# SO-16.net
KiCad netlist of a schematic drawn in EAGLE
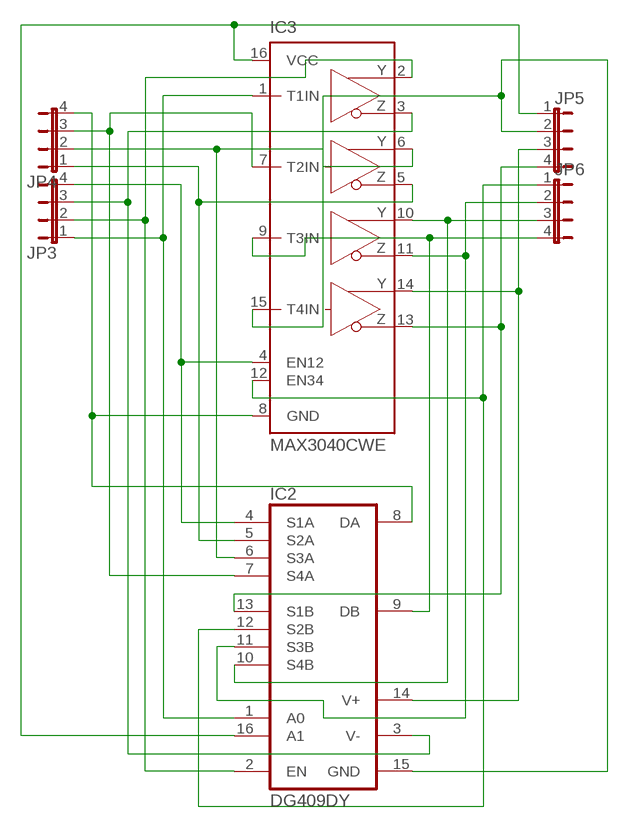
[diagram p0: schematic, sheet 1]

(export (version "E")
  (design (tool "Eeschema 10.0.6"))
  (components
    (comp (ref "IC2")
      (value "DG409DY")
      (footprint "eagle-import:SO16")
      (fields (field (name "MF") "MAXIM"))
      (libsource (lib "eagle-import") (part "DG409DY"))
    )
    (comp (ref "IC3")
      (value "MAX3040CWE")
      (footprint "eagle-import:SO16L")
      (fields (field (name "MPN") "MAX3040CWE+"))
      (libsource (lib "eagle-import") (part "MAX30WE40C"))
    )
    (comp (ref "JP3")
      (value "JP4E")
      (footprint "eagle-import:JP4")
      (libsource (lib "eagle-import") (part "JP4E"))
    )
    (comp (ref "JP4")
      (value "JP4E")
      (footprint "eagle-import:JP4")
      (libsource (lib "eagle-import") (part "JP4E"))
    )
    (comp (ref "JP5")
      (value "JP4E")
      (footprint "eagle-import:JP4")
      (libsource (lib "eagle-import") (part "JP4E"))
    )
    (comp (ref "JP6")
      (value "JP4E")
      (footprint "eagle-import:JP4")
      (libsource (lib "eagle-import") (part "JP4E"))
    )
  )
  (nets
    (net (code "1") (name "Net-(IC2-A0)") (class "Default")
      (node (ref "IC2") (pin "1") (pinfunction "A0_1") (pintype "input"))
      (node (ref "IC3") (pin "1") (pinfunction "T1IN_1") (pintype "input"))
      (node (ref "JP3") (pin "1") (pinfunction "1_1") (pintype "passive"))
    )
    (net (code "2") (name "Net-(IC2-A1)") (class "Default")
      (node (ref "IC2") (pin "16") (pinfunction "A1_16") (pintype "input"))
      (node (ref "IC3") (pin "16") (pinfunction "VCC_16") (pintype "power_in"))
      (node (ref "JP5") (pin "1") (pinfunction "1_1") (pintype "passive"))
    )
    (net (code "3") (name "Net-(IC2-DA)") (class "Default")
      (node (ref "IC2") (pin "8") (pinfunction "DA_8") (pintype "passive"))
      (node (ref "IC3") (pin "8") (pinfunction "GND_8") (pintype "power_in"))
      (node (ref "JP4") (pin "4") (pinfunction "4_4") (pintype "passive"))
    )
    (net (code "4") (name "Net-(IC2-DB)") (class "Default")
      (node (ref "IC2") (pin "9") (pinfunction "DB_9") (pintype "passive"))
      (node (ref "IC3") (pin "9") (pinfunction "T3IN_9") (pintype "input"))
      (node (ref "JP6") (pin "4") (pinfunction "4_4") (pintype "passive"))
    )
    (net (code "5") (name "Net-(IC2-EN)") (class "Default")
      (node (ref "IC2") (pin "2") (pinfunction "EN_2") (pintype "input"))
      (node (ref "IC3") (pin "2") (pinfunction "Y1_2") (pintype "output"))
      (node (ref "JP3") (pin "2") (pinfunction "2_2") (pintype "passive"))
    )
    (net (code "6") (name "Net-(IC2-GND)") (class "Default")
      (node (ref "IC2") (pin "15") (pinfunction "GND_15") (pintype "power_in"))
      (node (ref "IC3") (pin "15") (pinfunction "T4IN_15") (pintype "input"))
      (node (ref "JP5") (pin "2") (pinfunction "2_2") (pintype "passive"))
    )
    (net (code "7") (name "Net-(IC2-S1A)") (class "Default")
      (node (ref "IC2") (pin "4") (pinfunction "S1A_4") (pintype "passive"))
      (node (ref "IC3") (pin "4") (pinfunction "EN12_4") (pintype "input"))
      (node (ref "JP3") (pin "4") (pinfunction "4_4") (pintype "passive"))
    )
    (net (code "8") (name "Net-(IC2-S1B)") (class "Default")
      (node (ref "IC2") (pin "13") (pinfunction "S1B_13") (pintype "passive"))
      (node (ref "IC3") (pin "13") (pinfunction "Z4_13") (pintype "output"))
      (node (ref "JP5") (pin "4") (pinfunction "4_4") (pintype "passive"))
    )
    (net (code "9") (name "Net-(IC2-S2A)") (class "Default")
      (node (ref "IC2") (pin "5") (pinfunction "S2A_5") (pintype "passive"))
      (node (ref "IC3") (pin "5") (pinfunction "Z2_5") (pintype "output"))
      (node (ref "JP4") (pin "1") (pinfunction "1_1") (pintype "passive"))
    )
    (net (code "10") (name "Net-(IC2-S2B)") (class "Default")
      (node (ref "IC2") (pin "12") (pinfunction "S2B_12") (pintype "passive"))
      (node (ref "IC3") (pin "12") (pinfunction "EN34_12") (pintype "input"))
      (node (ref "JP6") (pin "1") (pinfunction "1_1") (pintype "passive"))
    )
    (net (code "11") (name "Net-(IC2-S3A)") (class "Default")
      (node (ref "IC2") (pin "6") (pinfunction "S3A_6") (pintype "passive"))
      (node (ref "IC3") (pin "6") (pinfunction "Y2_6") (pintype "output"))
      (node (ref "JP4") (pin "2") (pinfunction "2_2") (pintype "passive"))
    )
    (net (code "12") (name "Net-(IC2-S3B)") (class "Default")
      (node (ref "IC2") (pin "11") (pinfunction "S3B_11") (pintype "passive"))
      (node (ref "IC3") (pin "11") (pinfunction "Z3_11") (pintype "output"))
      (node (ref "JP6") (pin "2") (pinfunction "2_2") (pintype "passive"))
    )
    (net (code "13") (name "Net-(IC2-S4A)") (class "Default")
      (node (ref "IC2") (pin "7") (pinfunction "S4A_7") (pintype "passive"))
      (node (ref "IC3") (pin "7") (pinfunction "T2IN_7") (pintype "input"))
      (node (ref "JP4") (pin "3") (pinfunction "3_3") (pintype "passive"))
    )
    (net (code "14") (name "Net-(IC2-S4B)") (class "Default")
      (node (ref "IC2") (pin "10") (pinfunction "S4B_10") (pintype "passive"))
      (node (ref "IC3") (pin "10") (pinfunction "Y3_10") (pintype "output"))
      (node (ref "JP6") (pin "3") (pinfunction "3_3") (pintype "passive"))
    )
    (net (code "15") (name "Net-(IC2-V+)") (class "Default")
      (node (ref "IC2") (pin "14") (pinfunction "V+_14") (pintype "power_in"))
      (node (ref "IC3") (pin "14") (pinfunction "Y4_14") (pintype "output"))
      (node (ref "JP5") (pin "3") (pinfunction "3_3") (pintype "passive"))
    )
    (net (code "16") (name "Net-(IC2-V-)") (class "Default")
      (node (ref "IC2") (pin "3") (pinfunction "V-_3") (pintype "power_in"))
      (node (ref "IC3") (pin "3") (pinfunction "Z1_3") (pintype "output"))
      (node (ref "JP3") (pin "3") (pinfunction "3_3") (pintype "passive"))
    )
  )
)
